# SparkFun_RTK_Facet_-_Cellular.net
KiCad netlist of a schematic drawn in EAGLE
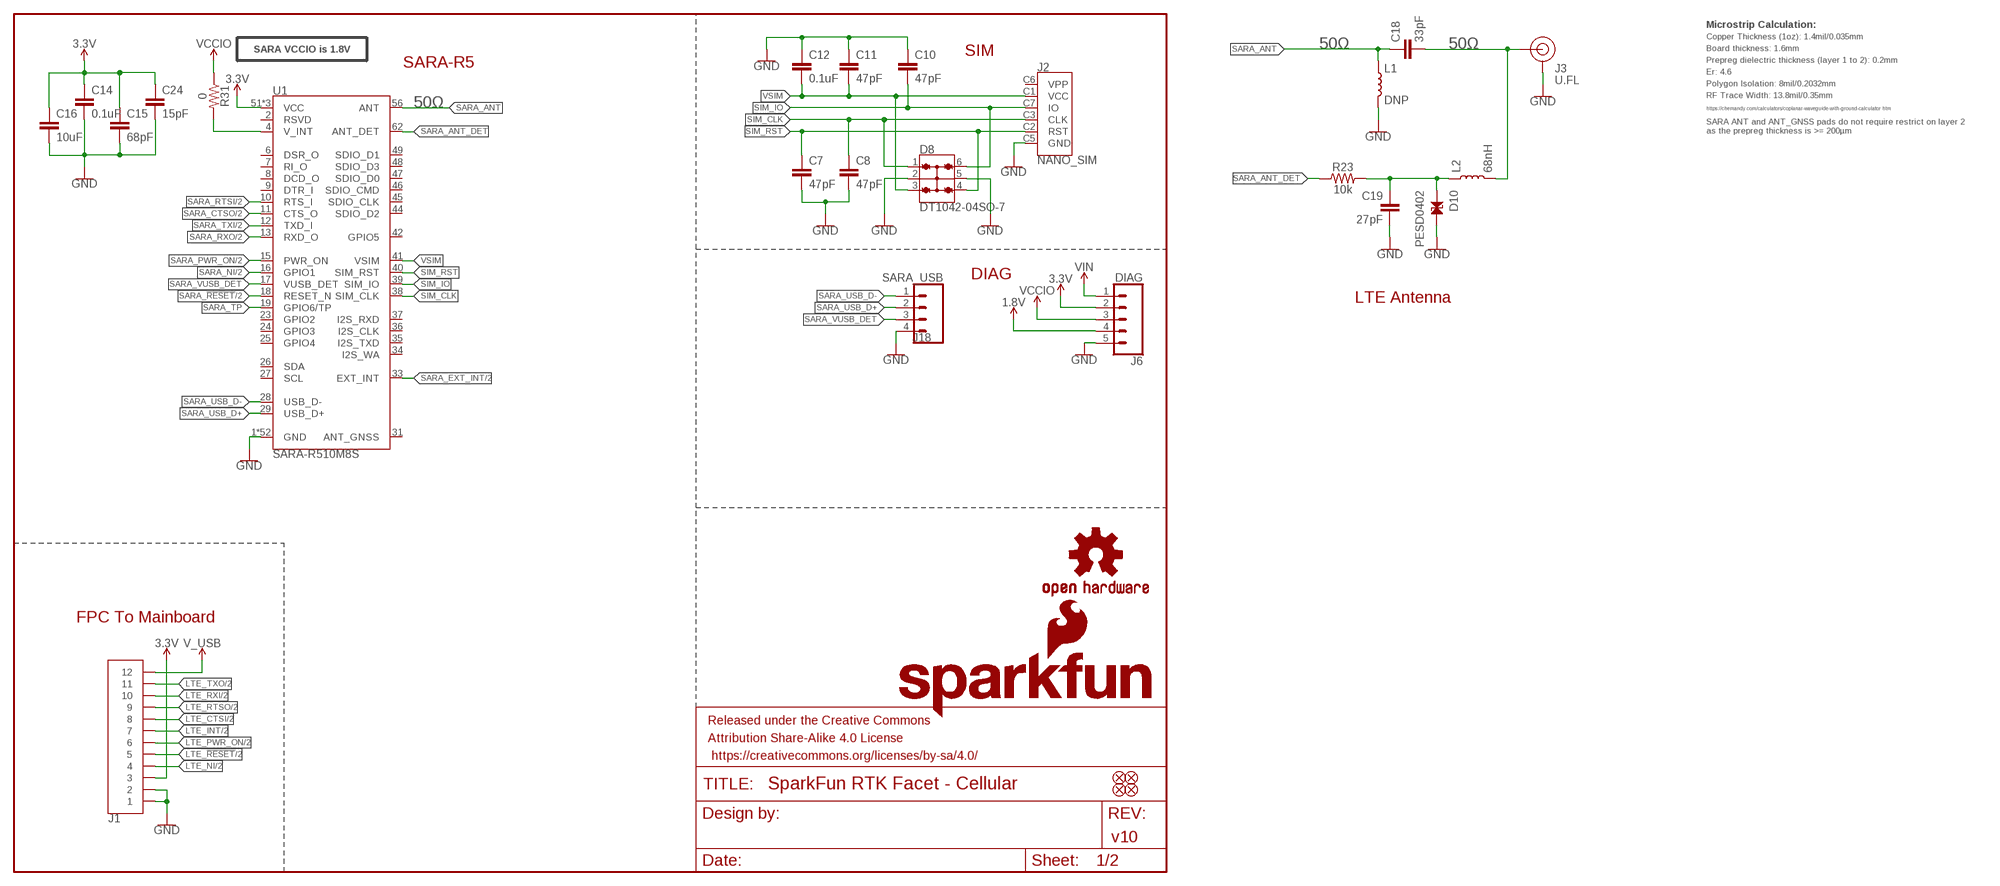
[diagram p0: schematic, sheet 1]
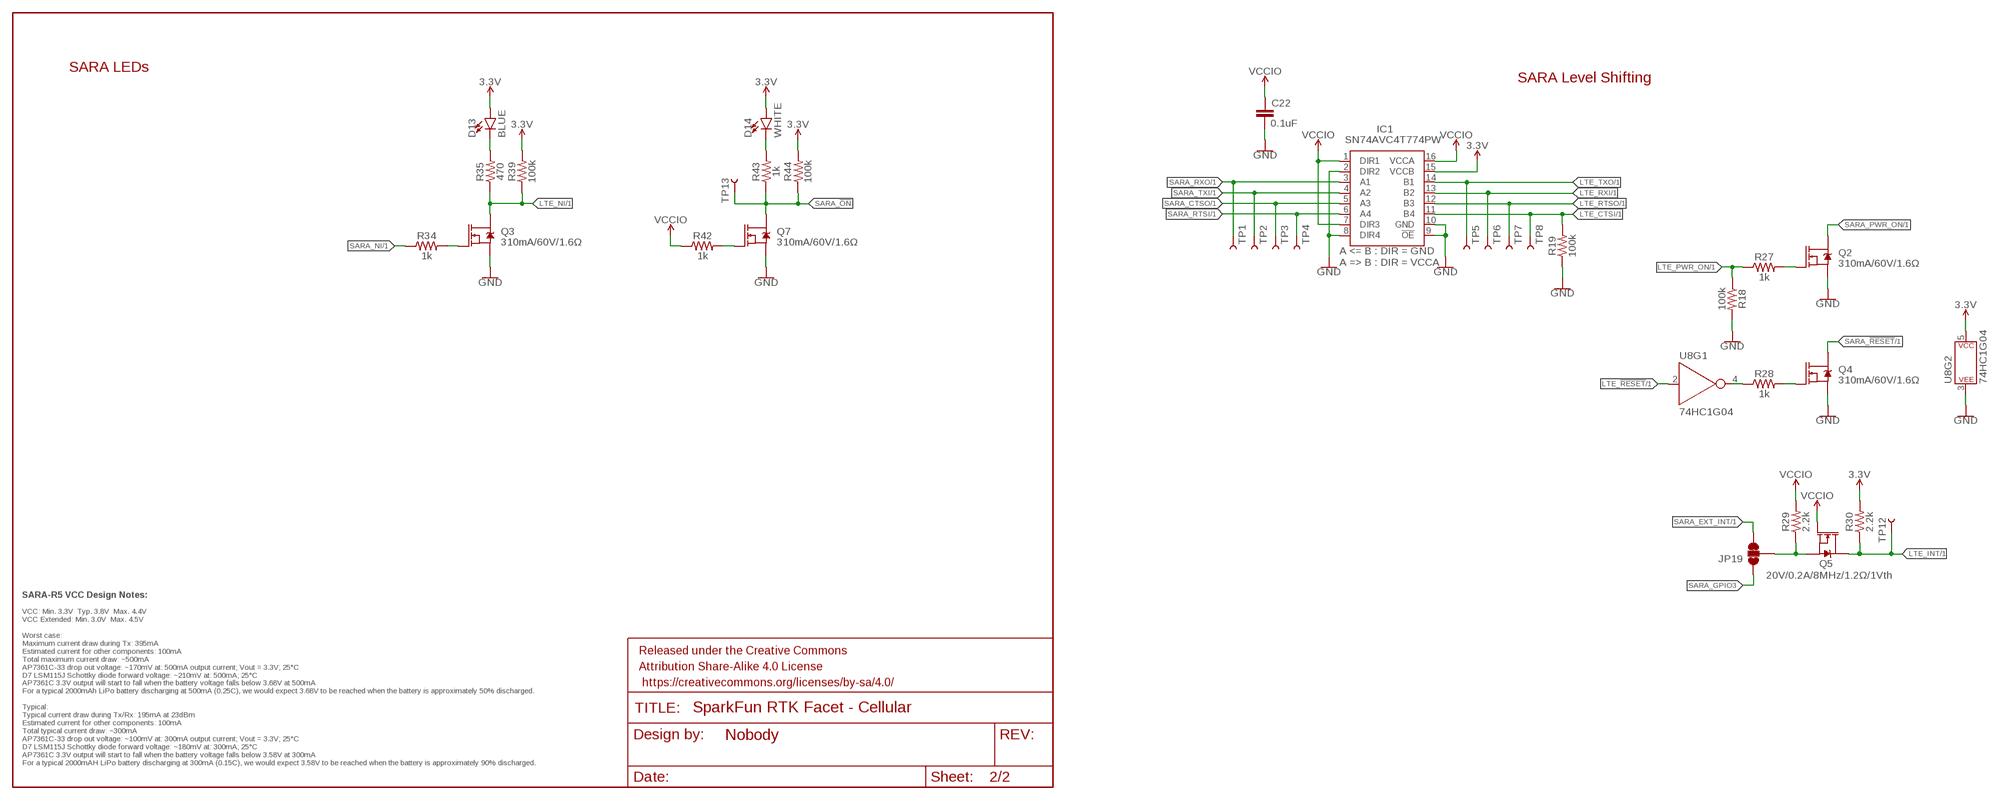
[diagram p1: schematic, sheet 2]

(export (version "E")
  (design (tool "Eeschema 10.0.6"))
  (components
    (comp (ref "C22")
      (value "0.1uF")
      (footprint "eagle-import:0603")
      (libsource (lib "eagle-import") (part "0.1UF-0603-25V-(+80/-20%)"))
    )
    (comp (ref "D13")
      (value "BLUE")
      (footprint "eagle-import:LED-0603")
      (libsource (lib "eagle-import") (part "LED-BLUE0603"))
    )
    (comp (ref "D14")
      (value "WHITE")
      (footprint "eagle-import:LED-0603")
      (libsource (lib "eagle-import") (part "LED-WHITE0603"))
    )
    (comp (ref "FRAME2")
      (value "FRAME-LETTERNO_PACKAGE")
      (footprint "eagle-import:DUMMY")
      (fields (field (name "DESIGNER") "Nobody"))
      (libsource (lib "eagle-import") (part "FRAME-LETTERNO_PACKAGE"))
    )
    (comp (ref "IC1")
      (value "SN74AVC4T774PW")
      (footprint "eagle-import:SOP65P640X120-16N")
      (fields (field (name "MOUSER_PART_NUMBER") "595-SN74AVC4T774PW"))
      (libsource (lib "eagle-import") (part "SN74AVC4T774PW"))
    )
    (comp (ref "JP19")
      (value "JUMPER-SMT_3_1-NC_TRACE_SILK")
      (footprint "eagle-import:SMT-JUMPER_3_1-NC_TRACE_SILK")
      (libsource (lib "eagle-import") (part "JUMPER-SMT_3_1-NC_TRACE_SILK"))
    )
    (comp (ref "Q2")
      (value "310mA/60V/1.6Ω")
      (footprint "eagle-import:SOT323")
      (libsource (lib "eagle-import") (part "MOSFET-NCH-2N7002PW"))
    )
    (comp (ref "Q3")
      (value "310mA/60V/1.6Ω")
      (footprint "eagle-import:SOT323")
      (libsource (lib "eagle-import") (part "MOSFET-NCH-2N7002PW"))
    )
    (comp (ref "Q4")
      (value "310mA/60V/1.6Ω")
      (footprint "eagle-import:SOT323")
      (libsource (lib "eagle-import") (part "MOSFET-NCH-2N7002PW"))
    )
    (comp (ref "Q5")
      (value "20V/0.2A/8MHz/1.2Ω/1Vth")
      (footprint "eagle-import:SOT-416FL")
      (libsource (lib "eagle-import") (part "MOSFET-NCH-RE1C00UNTL"))
    )
    (comp (ref "Q7")
      (value "310mA/60V/1.6Ω")
      (footprint "eagle-import:SOT323")
      (libsource (lib "eagle-import") (part "MOSFET-NCH-2N7002PW"))
    )
    (comp (ref "R18")
      (value "100k")
      (footprint "eagle-import:0603")
      (libsource (lib "eagle-import") (part "100KOHM-0603-1/10W-1%"))
    )
    (comp (ref "R19")
      (value "100k")
      (footprint "eagle-import:0603")
      (libsource (lib "eagle-import") (part "100KOHM-0603-1/10W-1%"))
    )
    (comp (ref "R27")
      (value "1k")
      (footprint "eagle-import:0603")
      (libsource (lib "eagle-import") (part "1KOHM-0603-1/10W-1%"))
    )
    (comp (ref "R28")
      (value "1k")
      (footprint "eagle-import:0603")
      (libsource (lib "eagle-import") (part "1KOHM-0603-1/10W-1%"))
    )
    (comp (ref "R29")
      (value "2.2k")
      (footprint "eagle-import:0603")
      (libsource (lib "eagle-import") (part "2.2KOHM-0603-1/10W-1%"))
    )
    (comp (ref "R30")
      (value "2.2k")
      (footprint "eagle-import:0603")
      (libsource (lib "eagle-import") (part "2.2KOHM-0603-1/10W-1%"))
    )
    (comp (ref "R34")
      (value "1k")
      (footprint "eagle-import:0603")
      (libsource (lib "eagle-import") (part "1KOHM-0603-1/10W-1%"))
    )
    (comp (ref "R35")
      (value "470")
      (footprint "eagle-import:0603")
      (libsource (lib "eagle-import") (part "470OHM-0603-1/10W-1%"))
    )
    (comp (ref "R39")
      (value "100k")
      (footprint "eagle-import:0603")
      (libsource (lib "eagle-import") (part "100KOHM-0603-1/10W-1%"))
    )
    (comp (ref "R42")
      (value "1k")
      (footprint "eagle-import:0603")
      (libsource (lib "eagle-import") (part "1KOHM-0603-1/10W-1%"))
    )
    (comp (ref "R43")
      (value "1k")
      (footprint "eagle-import:0603")
      (libsource (lib "eagle-import") (part "1KOHM-0603-1/10W-1%"))
    )
    (comp (ref "R44")
      (value "100k")
      (footprint "eagle-import:0603")
      (libsource (lib "eagle-import") (part "100KOHM-0603-1/10W-1%"))
    )
    (comp (ref "TP1")
      (value "TEST-POINT3")
      (footprint "eagle-import:PAD.03X.03")
      (libsource (lib "eagle-import") (part "TEST-POINT3"))
    )
    (comp (ref "TP2")
      (value "TEST-POINT3")
      (footprint "eagle-import:PAD.03X.03")
      (libsource (lib "eagle-import") (part "TEST-POINT3"))
    )
    (comp (ref "TP3")
      (value "TEST-POINT3")
      (footprint "eagle-import:PAD.03X.03")
      (libsource (lib "eagle-import") (part "TEST-POINT3"))
    )
    (comp (ref "TP4")
      (value "TEST-POINT3")
      (footprint "eagle-import:PAD.03X.03")
      (libsource (lib "eagle-import") (part "TEST-POINT3"))
    )
    (comp (ref "TP5")
      (value "TEST-POINT3")
      (footprint "eagle-import:PAD.03X.03")
      (libsource (lib "eagle-import") (part "TEST-POINT3"))
    )
    (comp (ref "TP6")
      (value "TEST-POINT3")
      (footprint "eagle-import:PAD.03X.03")
      (libsource (lib "eagle-import") (part "TEST-POINT3"))
    )
    (comp (ref "TP7")
      (value "TEST-POINT3")
      (footprint "eagle-import:PAD.03X.03")
      (libsource (lib "eagle-import") (part "TEST-POINT3"))
    )
    (comp (ref "TP8")
      (value "TEST-POINT3")
      (footprint "eagle-import:PAD.03X.03")
      (libsource (lib "eagle-import") (part "TEST-POINT3"))
    )
    (comp (ref "TP12")
      (value "TEST-POINT3")
      (footprint "eagle-import:PAD.03X.03")
      (libsource (lib "eagle-import") (part "TEST-POINT3"))
    )
    (comp (ref "TP13")
      (value "TEST-POINT3")
      (footprint "eagle-import:PAD.03X.03")
      (libsource (lib "eagle-import") (part "TEST-POINT3"))
    )
    (comp (ref "U8")
      (value "74HC1G04")
      (footprint "eagle-import:SOT353")
      (libsource (lib "eagle-import") (part "741G04HC"))
    )
    (comp (ref "C7")
      (value "47pF")
      (footprint "eagle-import:0603")
      (libsource (lib "eagle-import") (part "47PF-0603-50V-5%"))
    )
    (comp (ref "C8")
      (value "47pF")
      (footprint "eagle-import:0603")
      (libsource (lib "eagle-import") (part "47PF-0603-50V-5%"))
    )
    (comp (ref "C10")
      (value "47pF")
      (footprint "eagle-import:0603")
      (libsource (lib "eagle-import") (part "47PF-0603-50V-5%"))
    )
    (comp (ref "C11")
      (value "47pF")
      (footprint "eagle-import:0603")
      (libsource (lib "eagle-import") (part "47PF-0603-50V-5%"))
    )
    (comp (ref "C12")
      (value "0.1uF")
      (footprint "eagle-import:0603")
      (libsource (lib "eagle-import") (part "0.1UF-0603-25V-5%"))
    )
    (comp (ref "C14")
      (value "0.1uF")
      (footprint "eagle-import:0603")
      (libsource (lib "eagle-import") (part "0.1UF-0603-25V-5%"))
    )
    (comp (ref "C15")
      (value "68pF")
      (footprint "eagle-import:0603")
      (libsource (lib "eagle-import") (part "68PF-0603-50V-5%"))
    )
    (comp (ref "C16")
      (value "10uF")
      (footprint "eagle-import:0603")
      (libsource (lib "eagle-import") (part "10UF-0603-6.3V-20%"))
    )
    (comp (ref "C18")
      (value "33pF")
      (footprint "eagle-import:0402")
      (fields
        (field (name "DIGIKEY_PART") "490-5936-1-ND")
        (field (name "MANUFACTURER") "Murata")
        (field (name "MANU_PART") "GRM1555C1H330JA")
      )
      (libsource (lib "eagle-import") (part "33PF-0402-25V-5%-X7R"))
    )
    (comp (ref "C19")
      (value "27pF")
      (footprint "eagle-import:0402")
      (fields
        (field (name "DIGIKEY_PART") "490-11384-1-ND")
        (field (name "MANUFACTURER") "Murata")
        (field (name "MANU_PART") "GRM1555C1H270JA")
      )
      (libsource (lib "eagle-import") (part "27PF-0402-25V-5%-X7R"))
    )
    (comp (ref "C24")
      (value "15pF")
      (footprint "eagle-import:0603")
      (libsource (lib "eagle-import") (part "15PF-0603-50V-5%"))
    )
    (comp (ref "D8")
      (value "DT1042-04SO-7")
      (footprint "eagle-import:SOT23-6L")
      (libsource (lib "eagle-import") (part "TVS_DIODE_ARRAY_4DT1042-04SO-7"))
    )
    (comp (ref "D10")
      (value "PESD0402")
      (footprint "eagle-import:0402")
      (fields
        (field (name "DIGIKEY_PART") "PESD0402-140CT-ND")
        (field (name "MOUSE_PART") "650-PESD0402-140")
      )
      (libsource (lib "eagle-import") (part "PESD0402"))
    )
    (comp (ref "FID1")
      (value "FIDUCIAL1X2")
      (footprint "eagle-import:FIDUCIAL-1X2")
      (libsource (lib "eagle-import") (part "FIDUCIAL1X2"))
    )
    (comp (ref "FID2")
      (value "FIDUCIAL1X2")
      (footprint "eagle-import:FIDUCIAL-1X2")
      (libsource (lib "eagle-import") (part "FIDUCIAL1X2"))
    )
    (comp (ref "FID3")
      (value "FIDUCIAL1X2")
      (footprint "eagle-import:FIDUCIAL-1X2")
      (libsource (lib "eagle-import") (part "FIDUCIAL1X2"))
    )
    (comp (ref "FID4")
      (value "FIDUCIAL1X2")
      (footprint "eagle-import:FIDUCIAL-1X2")
      (libsource (lib "eagle-import") (part "FIDUCIAL1X2"))
    )
    (comp (ref "FRAME1")
      (value "FRAME-LETTER")
      (footprint "eagle-import:CREATIVE_COMMONS")
      (libsource (lib "eagle-import") (part "FRAME-LETTER"))
    )
    (comp (ref "J1")
      (value "FPC_12_0.5MM_BACKFLIP")
      (footprint "eagle-import:FPC_12_DOUBLESIDED_BACKFLIP")
      (libsource (lib "eagle-import") (part "FPC_12_0.5MM_BACKFLIP"))
    )
    (comp (ref "J2")
      (value "NANO_SIM")
      (footprint "eagle-import:NANO_SIM_WURTH_693043020611")
      (libsource (lib "eagle-import") (part "NANO_SIMWURTH"))
    )
    (comp (ref "J3")
      (value "U.FL")
      (footprint "eagle-import:U.FL")
      (libsource (lib "eagle-import") (part "U.FL2PIN"))
    )
    (comp (ref "J6")
      (value "DIAG")
      (footprint "eagle-import:1X05_NO_SILK")
      (libsource (lib "eagle-import") (part "CONN_05NO_SILK"))
    )
    (comp (ref "J18")
      (value "SARA_USB")
      (footprint "eagle-import:1X04_NO_SILK")
      (libsource (lib "eagle-import") (part "CONN_041X04_NO_SILK"))
    )
    (comp (ref "L1")
      (value "DNP")
      (footprint "eagle-import:0402_COILCRAFT")
      (libsource (lib "eagle-import") (part "INDUCTOR_DNP-0402"))
    )
    (comp (ref "L2")
      (value "68nH")
      (footprint "eagle-import:0402_COILCRAFT")
      (fields (field (name "DIGIKEY_PART") "490-2633-1-ND") (field (name "MOUSER_PART") "81-LQG15HS68NJ02D"))
      (libsource (lib "eagle-import") (part "68NH-0402"))
    )
    (comp (ref "LOGO3")
      (value "OSHW-LOGOMINI")
      (footprint "eagle-import:OSHW-LOGO-MINI")
      (libsource (lib "eagle-import") (part "OSHW-LOGOMINI"))
    )
    (comp (ref "LOGO5")
      (value "SFE_LOGO_NAME_FLAME.1_INCH")
      (footprint "eagle-import:SFE_LOGO_NAME_FLAME_.1")
      (libsource (lib "eagle-import") (part "SFE_LOGO_NAME_FLAME.1_INCH"))
    )
    (comp (ref "R23")
      (value "10k")
      (footprint "eagle-import:0603")
      (libsource (lib "eagle-import") (part "10KOHM-0603-1/10W-1%"))
    )
    (comp (ref "R31")
      (value "0")
      (footprint "eagle-import:0603")
      (libsource (lib "eagle-import") (part "0OHM-0603-1/10W"))
    )
    (comp (ref "U1")
      (value "SARA-R510M8S")
      (footprint "eagle-import:SARA-LGA")
      (libsource (lib "eagle-import") (part "SARA-R510M8S"))
    )
  )
  (nets
    (net (code "1") (name "1.8V") (class "Default")
      (node (ref "J6") (pin "4") (pinfunction "4_4") (pintype "passive"))
    )
    (net (code "2") (name "3.3V") (class "Default")
      (node (ref "C14") (pin "1") (pinfunction "1_1") (pintype "passive"))
      (node (ref "C15") (pin "1") (pinfunction "1_1") (pintype "passive"))
      (node (ref "C16") (pin "1") (pinfunction "1_1") (pintype "passive"))
      (node (ref "C24") (pin "1") (pinfunction "1_1") (pintype "passive"))
      (node (ref "D13") (pin "A") (pinfunction "A_A") (pintype "passive"))
      (node (ref "D14") (pin "A") (pinfunction "A_A") (pintype "passive"))
      (node (ref "IC1") (pin "15") (pinfunction "VCCB_15") (pintype "power_in"))
      (node (ref "J1") (pin "3") (pinfunction "3_3") (pintype "bidirectional"))
      (node (ref "J6") (pin "2") (pinfunction "2_2") (pintype "passive"))
      (node (ref "R30") (pin "2") (pinfunction "2_2") (pintype "passive"))
      (node (ref "R39") (pin "2") (pinfunction "2_2") (pintype "passive"))
      (node (ref "R44") (pin "2") (pinfunction "2_2") (pintype "passive"))
      (node (ref "U1") (pin "51") (pinfunction "VCC_51") (pintype "power_in"))
      (node (ref "U1") (pin "52") (pinfunction "VCC_52") (pintype "power_in"))
      (node (ref "U1") (pin "53") (pinfunction "VCC_53") (pintype "power_in"))
      (node (ref "U8") (pin "5") (pinfunction "P$V+_5") (pintype "bidirectional"))
    )
    (net (code "3") (name "GND") (class "Default")
      (node (ref "C10") (pin "1") (pinfunction "1_1") (pintype "passive"))
      (node (ref "C11") (pin "1") (pinfunction "1_1") (pintype "passive"))
      (node (ref "C12") (pin "1") (pinfunction "1_1") (pintype "passive"))
      (node (ref "C14") (pin "2") (pinfunction "2_2") (pintype "passive"))
      (node (ref "C15") (pin "2") (pinfunction "2_2") (pintype "passive"))
      (node (ref "C16") (pin "2") (pinfunction "2_2") (pintype "passive"))
      (node (ref "C19") (pin "2") (pinfunction "2_2") (pintype "passive"))
      (node (ref "C22") (pin "2") (pinfunction "2_2") (pintype "passive"))
      (node (ref "C24") (pin "2") (pinfunction "2_2") (pintype "passive"))
      (node (ref "C7") (pin "2") (pinfunction "2_2") (pintype "passive"))
      (node (ref "C8") (pin "2") (pinfunction "2_2") (pintype "passive"))
      (node (ref "D10") (pin "2") (pinfunction "2_2") (pintype "bidirectional"))
      (node (ref "D8") (pin "2") (pinfunction "2_2") (pintype "bidirectional"))
      (node (ref "D8") (pin "5") (pinfunction "5_5") (pintype "bidirectional"))
      (node (ref "IC1") (pin "10") (pinfunction "GND_10") (pintype "power_in"))
      (node (ref "IC1") (pin "2") (pinfunction "DIR2_2") (pintype "input"))
      (node (ref "IC1") (pin "8") (pinfunction "DIR4_8") (pintype "input"))
      (node (ref "IC1") (pin "9") (pinfunction "~{OE}_9") (pintype "input"))
      (node (ref "J1") (pin "1") (pinfunction "1_1") (pintype "bidirectional"))
      (node (ref "J1") (pin "2") (pinfunction "2_2") (pintype "bidirectional"))
      (node (ref "J18") (pin "4") (pinfunction "4_4") (pintype "passive"))
      (node (ref "J2") (pin "C5") (pinfunction "GND_C5") (pintype "bidirectional"))
      (node (ref "J3") (pin "1") (pinfunction "GND_1") (pintype "bidirectional"))
      (node (ref "J3") (pin "2") (pinfunction "GND_2") (pintype "bidirectional"))
      (node (ref "J6") (pin "5") (pinfunction "5_5") (pintype "passive"))
      (node (ref "L1") (pin "P$2") (pinfunction "2_P$2") (pintype "passive"))
      (node (ref "Q2") (pin "2") (pinfunction "S_2") (pintype "bidirectional"))
      (node (ref "Q3") (pin "2") (pinfunction "S_2") (pintype "bidirectional"))
      (node (ref "Q4") (pin "2") (pinfunction "S_2") (pintype "bidirectional"))
      (node (ref "Q7") (pin "2") (pinfunction "S_2") (pintype "bidirectional"))
      (node (ref "R18") (pin "2") (pinfunction "2_2") (pintype "passive"))
      (node (ref "R19") (pin "1") (pinfunction "1_1") (pintype "passive"))
      (node (ref "U1") (pin "1") (pinfunction "GND_1") (pintype "power_in"))
      (node (ref "U1") (pin "14") (pinfunction "GND_14") (pintype "power_in"))
      (node (ref "U1") (pin "20") (pinfunction "GND_20") (pintype "power_in"))
      (node (ref "U1") (pin "21") (pinfunction "GND_21") (pintype "power_in"))
      (node (ref "U1") (pin "22") (pinfunction "GND_22") (pintype "power_in"))
      (node (ref "U1") (pin "3") (pinfunction "GND_3") (pintype "power_in"))
      (node (ref "U1") (pin "30") (pinfunction "GND_30") (pintype "power_in"))
      (node (ref "U1") (pin "32") (pinfunction "GND_32") (pintype "power_in"))
      (node (ref "U1") (pin "43") (pinfunction "GND_43") (pintype "power_in"))
      (node (ref "U1") (pin "5") (pinfunction "GND_5") (pintype "power_in"))
      (node (ref "U1") (pin "50") (pinfunction "GND_50") (pintype "power_in"))
      (node (ref "U1") (pin "54") (pinfunction "GND_54") (pintype "power_in"))
      (node (ref "U1") (pin "55") (pinfunction "GND_55") (pintype "power_in"))
      (node (ref "U1") (pin "57") (pinfunction "GND_57") (pintype "power_in"))
      (node (ref "U1") (pin "58") (pinfunction "GND_58") (pintype "power_in"))
      (node (ref "U1") (pin "59") (pinfunction "GND_59") (pintype "power_in"))
      (node (ref "U1") (pin "60") (pinfunction "GND_60") (pintype "power_in"))
      (node (ref "U1") (pin "61") (pinfunction "GND_61") (pintype "power_in"))
      (node (ref "U1") (pin "63") (pinfunction "GND_63") (pintype "power_in"))
      (node (ref "U1") (pin "64") (pinfunction "GND_64") (pintype "power_in"))
      (node (ref "U1") (pin "65") (pinfunction "GND_65") (pintype "power_in"))
      (node (ref "U1") (pin "66") (pinfunction "GND_66") (pintype "power_in"))
      (node (ref "U1") (pin "67") (pinfunction "GND_67") (pintype "power_in"))
      (node (ref "U1") (pin "68") (pinfunction "GND_68") (pintype "power_in"))
      (node (ref "U1") (pin "69") (pinfunction "GND_69") (pintype "power_in"))
      (node (ref "U1") (pin "70") (pinfunction "GND_70") (pintype "power_in"))
      (node (ref "U1") (pin "71") (pinfunction "GND_71") (pintype "power_in"))
      (node (ref "U1") (pin "72") (pinfunction "GND_72") (pintype "power_in"))
      (node (ref "U1") (pin "73") (pinfunction "GND_73") (pintype "power_in"))
      (node (ref "U1") (pin "74") (pinfunction "GND_74") (pintype "power_in"))
      (node (ref "U1") (pin "75") (pinfunction "GND_75") (pintype "power_in"))
      (node (ref "U1") (pin "76") (pinfunction "GND_76") (pintype "power_in"))
      (node (ref "U1") (pin "77") (pinfunction "GND_77") (pintype "power_in"))
      (node (ref "U1") (pin "78") (pinfunction "GND_78") (pintype "power_in"))
      (node (ref "U1") (pin "79") (pinfunction "GND_79") (pintype "power_in"))
      (node (ref "U1") (pin "80") (pinfunction "GND_80") (pintype "power_in"))
      (node (ref "U1") (pin "81") (pinfunction "GND_81") (pintype "power_in"))
      (node (ref "U1") (pin "82") (pinfunction "GND_82") (pintype "power_in"))
      (node (ref "U1") (pin "83") (pinfunction "GND_83") (pintype "power_in"))
      (node (ref "U1") (pin "84") (pinfunction "GND_84") (pintype "power_in"))
      (node (ref "U1") (pin "85") (pinfunction "GND_85") (pintype "power_in"))
      (node (ref "U1") (pin "86") (pinfunction "GND_86") (pintype "power_in"))
      (node (ref "U1") (pin "87") (pinfunction "GND_87") (pintype "power_in"))
      (node (ref "U1") (pin "88") (pinfunction "GND_88") (pintype "power_in"))
      (node (ref "U1") (pin "89") (pinfunction "GND_89") (pintype "power_in"))
      (node (ref "U1") (pin "90") (pinfunction "GND_90") (pintype "power_in"))
      (node (ref "U1") (pin "91") (pinfunction "GND_91") (pintype "power_in"))
      (node (ref "U1") (pin "92") (pinfunction "GND_92") (pintype "power_in"))
      (node (ref "U1") (pin "93") (pinfunction "GND_93") (pintype "power_in"))
      (node (ref "U1") (pin "94") (pinfunction "GND_94") (pintype "power_in"))
      (node (ref "U1") (pin "95") (pinfunction "GND_95") (pintype "power_in"))
      (node (ref "U1") (pin "96") (pinfunction "GND_96") (pintype "power_in"))
      (node (ref "U8") (pin "3") (pinfunction "P$V-_3") (pintype "bidirectional"))
    )
    (net (code "4") (name "LTE_CTSI") (class "Default")
      (node (ref "IC1") (pin "11") (pinfunction "B4_11") (pintype "bidirectional"))
      (node (ref "J1") (pin "8") (pinfunction "8_8") (pintype "bidirectional"))
      (node (ref "R19") (pin "2") (pinfunction "2_2") (pintype "passive"))
      (node (ref "TP8") (pin "P$1") (pinfunction "1_P$1") (pintype "bidirectional"))
    )
    (net (code "5") (name "LTE_INT") (class "Default")
      (node (ref "J1") (pin "7") (pinfunction "7_7") (pintype "bidirectional"))
      (node (ref "Q5") (pin "3") (pinfunction "D_3") (pintype "bidirectional"))
      (node (ref "R30") (pin "1") (pinfunction "1_1") (pintype "passive"))
      (node (ref "TP12") (pin "P$1") (pinfunction "1_P$1") (pintype "bidirectional"))
    )
    (net (code "6") (name "LTE_NI") (class "Default")
      (node (ref "J1") (pin "4") (pinfunction "4_4") (pintype "bidirectional"))
      (node (ref "Q3") (pin "3") (pinfunction "D_3") (pintype "bidirectional"))
      (node (ref "R35") (pin "1") (pinfunction "1_1") (pintype "passive"))
      (node (ref "R39") (pin "1") (pinfunction "1_1") (pintype "passive"))
    )
    (net (code "7") (name "LTE_PWR_ON") (class "Default")
      (node (ref "J1") (pin "6") (pinfunction "6_6") (pintype "bidirectional"))
      (node (ref "R18") (pin "1") (pinfunction "1_1") (pintype "passive"))
      (node (ref "R27") (pin "1") (pinfunction "1_1") (pintype "passive"))
    )
    (net (code "8") (name "LTE_RTSO") (class "Default")
      (node (ref "IC1") (pin "12") (pinfunction "B3_12") (pintype "bidirectional"))
      (node (ref "J1") (pin "9") (pinfunction "9_9") (pintype "bidirectional"))
      (node (ref "TP7") (pin "P$1") (pinfunction "1_P$1") (pintype "bidirectional"))
    )
    (net (code "9") (name "LTE_RXI") (class "Default")
      (node (ref "IC1") (pin "13") (pinfunction "B2_13") (pintype "bidirectional"))
      (node (ref "J1") (pin "10") (pinfunction "10_10") (pintype "bidirectional"))
      (node (ref "TP6") (pin "P$1") (pinfunction "1_P$1") (pintype "bidirectional"))
    )
    (net (code "10") (name "LTE_TXO") (class "Default")
      (node (ref "IC1") (pin "14") (pinfunction "B1_14") (pintype "bidirectional"))
      (node (ref "J1") (pin "11") (pinfunction "11_11") (pintype "bidirectional"))
      (node (ref "TP5") (pin "P$1") (pinfunction "1_P$1") (pintype "bidirectional"))
    )
    (net (code "11") (name "LTE_~{RESET}") (class "Default")
      (node (ref "J1") (pin "5") (pinfunction "5_5") (pintype "bidirectional"))
      (node (ref "U8") (pin "2") (pinfunction "A_2") (pintype "bidirectional"))
    )
    (net (code "12") (name "Net-(D13-PadC)") (class "Default")
      (node (ref "D13") (pin "C") (pinfunction "C_C") (pintype "passive"))
      (node (ref "R35") (pin "2") (pinfunction "2_2") (pintype "passive"))
    )
    (net (code "13") (name "Net-(D14-PadC)") (class "Default")
      (node (ref "D14") (pin "C") (pinfunction "C_C") (pintype "passive"))
      (node (ref "R43") (pin "2") (pinfunction "2_2") (pintype "passive"))
    )
    (net (code "14") (name "Net-(J3-SIGNAL)") (class "Default")
      (node (ref "C18") (pin "2") (pinfunction "2_2") (pintype "passive"))
      (node (ref "J3") (pin "FEED") (pinfunction "SIGNAL_FEED") (pintype "bidirectional"))
      (node (ref "L2") (pin "P$2") (pinfunction "2_P$2") (pintype "passive"))
    )
    (net (code "15") (name "Net-(L2-1)") (class "Default")
      (node (ref "C19") (pin "1") (pinfunction "1_1") (pintype "passive"))
      (node (ref "D10") (pin "1") (pinfunction "1_1") (pintype "bidirectional"))
      (node (ref "L2") (pin "P$1") (pinfunction "1_P$1") (pintype "passive"))
      (node (ref "R23") (pin "2") (pinfunction "2_2") (pintype "passive"))
    )
    (net (code "16") (name "Net-(Q2-G)") (class "Default")
      (node (ref "Q2") (pin "1") (pinfunction "G_1") (pintype "bidirectional"))
      (node (ref "R27") (pin "2") (pinfunction "2_2") (pintype "passive"))
    )
    (net (code "17") (name "Net-(Q3-G)") (class "Default")
      (node (ref "Q3") (pin "1") (pinfunction "G_1") (pintype "bidirectional"))
      (node (ref "R34") (pin "2") (pinfunction "2_2") (pintype "passive"))
    )
    (net (code "18") (name "Net-(Q4-G)") (class "Default")
      (node (ref "Q4") (pin "1") (pinfunction "G_1") (pintype "bidirectional"))
      (node (ref "R28") (pin "2") (pinfunction "2_2") (pintype "passive"))
    )
    (net (code "19") (name "Net-(Q5-S)") (class "Default")
      (node (ref "JP19") (pin "2") (pinfunction "2_2") (pintype "passive"))
      (node (ref "Q5") (pin "2") (pinfunction "S_2") (pintype "bidirectional"))
      (node (ref "R29") (pin "1") (pinfunction "1_1") (pintype "passive"))
    )
    (net (code "20") (name "Net-(Q7-G)") (class "Default")
      (node (ref "Q7") (pin "1") (pinfunction "G_1") (pintype "bidirectional"))
      (node (ref "R42") (pin "2") (pinfunction "2_2") (pintype "passive"))
    )
    (net (code "21") (name "Net-(U1-V_INT)") (class "Default")
      (node (ref "R31") (pin "2") (pinfunction "2_2") (pintype "passive"))
      (node (ref "U1") (pin "4") (pinfunction "V_INT_4") (pintype "output"))
    )
    (net (code "22") (name "Net-(U8A-Y)") (class "Default")
      (node (ref "R28") (pin "1") (pinfunction "1_1") (pintype "passive"))
      (node (ref "U8") (pin "4") (pinfunction "Y_4") (pintype "bidirectional"))
    )
    (net (code "23") (name "SARA_ANT") (class "Default")
      (node (ref "C18") (pin "1") (pinfunction "1_1") (pintype "passive"))
      (node (ref "L1") (pin "P$1") (pinfunction "1_P$1") (pintype "passive"))
      (node (ref "U1") (pin "56") (pinfunction "ANT_56") (pintype "bidirectional"))
    )
    (net (code "24") (name "SARA_ANT_DET") (class "Default")
      (node (ref "R23") (pin "1") (pinfunction "1_1") (pintype "passive"))
      (node (ref "U1") (pin "62") (pinfunction "ANT_DET_62") (pintype "input"))
    )
    (net (code "25") (name "SARA_CTSO") (class "Default")
      (node (ref "IC1") (pin "5") (pinfunction "A3_5") (pintype "bidirectional"))
      (node (ref "TP3") (pin "P$1") (pinfunction "1_P$1") (pintype "bidirectional"))
      (node (ref "U1") (pin "11") (pinfunction "CTS_O_11") (pintype "output"))
    )
    (net (code "26") (name "SARA_EXT_INT") (class "Default")
      (node (ref "JP19") (pin "3") (pinfunction "3_3") (pintype "passive"))
      (node (ref "U1") (pin "33") (pinfunction "EXT_INT_33") (pintype "input"))
    )
    (net (code "27") (name "SARA_GPIO3") (class "Default")
      (node (ref "JP19") (pin "1") (pinfunction "1_1") (pintype "passive"))
    )
    (net (code "28") (name "SARA_NI") (class "Default")
      (node (ref "R34") (pin "1") (pinfunction "1_1") (pintype "passive"))
      (node (ref "U1") (pin "16") (pinfunction "GPIO1_16") (pintype "bidirectional"))
    )
    (net (code "29") (name "SARA_PWR_ON") (class "Default")
      (node (ref "Q2") (pin "3") (pinfunction "D_3") (pintype "bidirectional"))
      (node (ref "U1") (pin "15") (pinfunction "PWR_ON_15") (pintype "input"))
    )
    (net (code "30") (name "SARA_RTSI") (class "Default")
      (node (ref "IC1") (pin "6") (pinfunction "A4_6") (pintype "bidirectional"))
      (node (ref "TP4") (pin "P$1") (pinfunction "1_P$1") (pintype "bidirectional"))
      (node (ref "U1") (pin "10") (pinfunction "RTS_I_10") (pintype "input"))
    )
    (net (code "31") (name "SARA_RXO") (class "Default")
      (node (ref "IC1") (pin "3") (pinfunction "A1_3") (pintype "bidirectional"))
      (node (ref "TP1") (pin "P$1") (pinfunction "1_P$1") (pintype "bidirectional"))
      (node (ref "U1") (pin "13") (pinfunction "RXD_O_13") (pintype "output"))
    )
    (net (code "32") (name "SARA_TP") (class "Default")
      (node (ref "U1") (pin "19") (pinfunction "GPIO6/TP_19") (pintype "bidirectional"))
    )
    (net (code "33") (name "SARA_TXI") (class "Default")
      (node (ref "IC1") (pin "4") (pinfunction "A2_4") (pintype "bidirectional"))
      (node (ref "TP2") (pin "P$1") (pinfunction "1_P$1") (pintype "bidirectional"))
      (node (ref "U1") (pin "12") (pinfunction "TXD_I_12") (pintype "input"))
    )
    (net (code "34") (name "SARA_USB_D+") (class "Default")
      (node (ref "J18") (pin "2") (pinfunction "2_2") (pintype "passive"))
      (node (ref "U1") (pin "29") (pinfunction "USB_D+_29") (pintype "bidirectional"))
    )
    (net (code "35") (name "SARA_USB_D-") (class "Default")
      (node (ref "J18") (pin "1") (pinfunction "1_1") (pintype "passive"))
      (node (ref "U1") (pin "28") (pinfunction "USB_D-_28") (pintype "bidirectional"))
    )
    (net (code "36") (name "SARA_VUSB_DET") (class "Default")
      (node (ref "J18") (pin "3") (pinfunction "3_3") (pintype "passive"))
      (node (ref "U1") (pin "17") (pinfunction "VUSB_DET_17") (pintype "input"))
    )
    (net (code "37") (name "SARA_~{ON}") (class "Default")
      (node (ref "Q7") (pin "3") (pinfunction "D_3") (pintype "bidirectional"))
      (node (ref "R43") (pin "1") (pinfunction "1_1") (pintype "passive"))
      (node (ref "R44") (pin "1") (pinfunction "1_1") (pintype "passive"))
      (node (ref "TP13") (pin "P$1") (pinfunction "1_P$1") (pintype "bidirectional"))
    )
    (net (code "38") (name "SARA_~{RESET}") (class "Default")
      (node (ref "Q4") (pin "3") (pinfunction "D_3") (pintype "bidirectional"))
      (node (ref "U1") (pin "18") (pinfunction "RESET_N_18") (pintype "input"))
    )
    (net (code "39") (name "SIM_CLK") (class "Default")
      (node (ref "C8") (pin "1") (pinfunction "1_1") (pintype "passive"))
      (node (ref "D8") (pin "1") (pinfunction "1_1") (pintype "bidirectional"))
      (node (ref "J2") (pin "C3") (pinfunction "CLK_C3") (pintype "bidirectional"))
      (node (ref "U1") (pin "38") (pinfunction "SIM_CLK_38") (pintype "output"))
    )
    (net (code "40") (name "SIM_IO") (class "Default")
      (node (ref "C10") (pin "2") (pinfunction "2_2") (pintype "passive"))
      (node (ref "D8") (pin "6") (pinfunction "6_6") (pintype "bidirectional"))
      (node (ref "J2") (pin "C7") (pinfunction "IO_C7") (pintype "bidirectional"))
      (node (ref "U1") (pin "39") (pinfunction "SIM_IO_39") (pintype "bidirectional"))
    )
    (net (code "41") (name "SIM_RST") (class "Default")
      (node (ref "C7") (pin "1") (pinfunction "1_1") (pintype "passive"))
      (node (ref "D8") (pin "4") (pinfunction "4_4") (pintype "bidirectional"))
      (node (ref "J2") (pin "C2") (pinfunction "RST_C2") (pintype "bidirectional"))
      (node (ref "U1") (pin "40") (pinfunction "SIM_RST_40") (pintype "output"))
    )
    (net (code "42") (name "VCCIO") (class "Default")
      (node (ref "C22") (pin "1") (pinfunction "1_1") (pintype "passive"))
      (node (ref "IC1") (pin "1") (pinfunction "DIR1_1") (pintype "input"))
      (node (ref "IC1") (pin "16") (pinfunction "VCCA_16") (pintype "power_in"))
      (node (ref "IC1") (pin "7") (pinfunction "DIR3_7") (pintype "input"))
      (node (ref "J6") (pin "3") (pinfunction "3_3") (pintype "passive"))
      (node (ref "Q5") (pin "1") (pinfunction "G_1") (pintype "bidirectional"))
      (node (ref "R29") (pin "2") (pinfunction "2_2") (pintype "passive"))
      (node (ref "R31") (pin "1") (pinfunction "1_1") (pintype "passive"))
      (node (ref "R42") (pin "1") (pinfunction "1_1") (pintype "passive"))
    )
    (net (code "43") (name "VIN") (class "Default")
      (node (ref "J6") (pin "1") (pinfunction "1_1") (pintype "passive"))
    )
    (net (code "44") (name "VSIM") (class "Default")
      (node (ref "C11") (pin "2") (pinfunction "2_2") (pintype "passive"))
      (node (ref "C12") (pin "2") (pinfunction "2_2") (pintype "passive"))
      (node (ref "D8") (pin "3") (pinfunction "3_3") (pintype "bidirectional"))
      (node (ref "J2") (pin "C1") (pinfunction "VCC_C1") (pintype "bidirectional"))
      (node (ref "U1") (pin "41") (pinfunction "VSIM_41") (pintype "output"))
    )
    (net (code "45") (name "V_USB") (class "Default")
      (node (ref "J1") (pin "12") (pinfunction "12_12") (pintype "bidirectional"))
    )
    (net (code "46") (name "unconnected-(J2-VPP-PadC6)") (class "Default")
      (node (ref "J2") (pin "C6") (pinfunction "VPP_C6") (pintype "bidirectional"))
    )
    (net (code "47") (name "unconnected-(U1-ANT_GNSS-Pad31)") (class "Default")
      (node (ref "U1") (pin "31") (pinfunction "ANT_GNSS_31") (pintype "input"))
    )
    (net (code "48") (name "unconnected-(U1-DCD_O-Pad8)") (class "Default")
      (node (ref "U1") (pin "8") (pinfunction "DCD_O_8") (pintype "output"))
    )
    (net (code "49") (name "unconnected-(U1-DSR_O-Pad6)") (class "Default")
      (node (ref "U1") (pin "6") (pinfunction "DSR_O_6") (pintype "output"))
    )
    (net (code "50") (name "unconnected-(U1-DTR_I-Pad9)") (class "Default")
      (node (ref "U1") (pin "9") (pinfunction "DTR_I_9") (pintype "input"))
    )
    (net (code "51") (name "unconnected-(U1-GPIO2-Pad23)") (class "Default")
      (node (ref "U1") (pin "23") (pinfunction "GPIO2_23") (pintype "bidirectional"))
    )
    (net (code "52") (name "unconnected-(U1-GPIO3-Pad24)") (class "Default")
      (node (ref "U1") (pin "24") (pinfunction "GPIO3_24") (pintype "bidirectional"))
    )
    (net (code "53") (name "unconnected-(U1-GPIO4-Pad25)") (class "Default")
      (node (ref "U1") (pin "25") (pinfunction "GPIO4_25") (pintype "bidirectional"))
    )
    (net (code "54") (name "unconnected-(U1-GPIO5-Pad42)") (class "Default")
      (node (ref "U1") (pin "42") (pinfunction "GPIO5_42") (pintype "bidirectional"))
    )
    (net (code "55") (name "unconnected-(U1-I2S_CLK-Pad36)") (class "Default")
      (node (ref "U1") (pin "36") (pinfunction "I2S_CLK_36") (pintype "output"))
    )
    (net (code "56") (name "unconnected-(U1-I2S_RXD-Pad37)") (class "Default")
      (node (ref "U1") (pin "37") (pinfunction "I2S_RXD_37") (pintype "input"))
    )
    (net (code "57") (name "unconnected-(U1-I2S_TXD-Pad35)") (class "Default")
      (node (ref "U1") (pin "35") (pinfunction "I2S_TXD_35") (pintype "output"))
    )
    (net (code "58") (name "unconnected-(U1-I2S_WA-Pad34)") (class "Default")
      (node (ref "U1") (pin "34") (pinfunction "I2S_WA_34") (pintype "output"))
    )
    (net (code "59") (name "unconnected-(U1-RI_O-Pad7)") (class "Default")
      (node (ref "U1") (pin "7") (pinfunction "RI_O_7") (pintype "output"))
    )
    (net (code "60") (name "unconnected-(U1-RSVD-Pad2)") (class "Default")
      (node (ref "U1") (pin "2") (pinfunction "RSVD_2") (pintype "no_connect"))
    )
    (net (code "61") (name "unconnected-(U1-SCL-Pad27)") (class "Default")
      (node (ref "U1") (pin "27") (pinfunction "SCL_27") (pintype "bidirectional"))
    )
    (net (code "62") (name "unconnected-(U1-SDA-Pad26)") (class "Default")
      (node (ref "U1") (pin "26") (pinfunction "SDA_26") (pintype "bidirectional"))
    )
    (net (code "63") (name "unconnected-(U1-SDIO_CLK-Pad45)") (class "Default")
      (node (ref "U1") (pin "45") (pinfunction "SDIO_CLK_45") (pintype "output"))
    )
    (net (code "64") (name "unconnected-(U1-SDIO_CMD-Pad46)") (class "Default")
      (node (ref "U1") (pin "46") (pinfunction "SDIO_CMD_46") (pintype "bidirectional"))
    )
    (net (code "65") (name "unconnected-(U1-SDIO_D0-Pad47)") (class "Default")
      (node (ref "U1") (pin "47") (pinfunction "SDIO_D0_47") (pintype "bidirectional"))
    )
    (net (code "66") (name "unconnected-(U1-SDIO_D1-Pad49)") (class "Default")
      (node (ref "U1") (pin "49") (pinfunction "SDIO_D1_49") (pintype "bidirectional"))
    )
    (net (code "67") (name "unconnected-(U1-SDIO_D2-Pad44)") (class "Default")
      (node (ref "U1") (pin "44") (pinfunction "SDIO_D2_44") (pintype "bidirectional"))
    )
    (net (code "68") (name "unconnected-(U1-SDIO_D3-Pad48)") (class "Default")
      (node (ref "U1") (pin "48") (pinfunction "SDIO_D3_48") (pintype "bidirectional"))
    )
  )
)
